# voltage_translation.net
KiCad netlist of a schematic drawn in Altium Designer
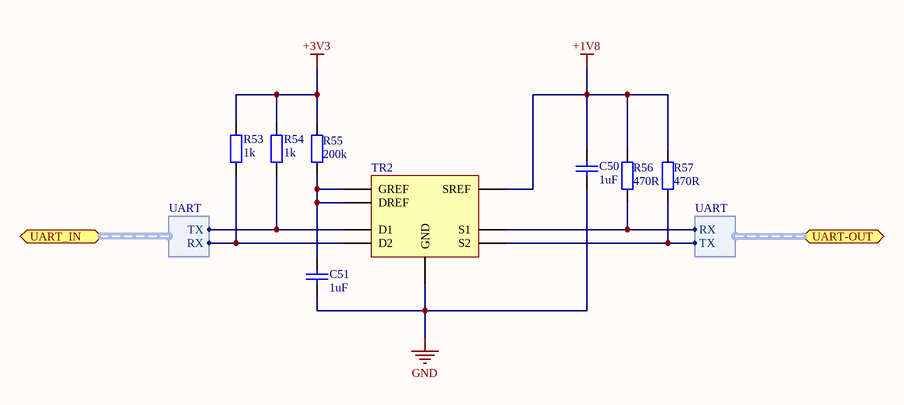
[diagram p0: voltage_translation.SchDoc]

(export (version "E")
  (design (tool "Eeschema 10.0.6"))
  (components
    (comp (ref "C50")
      (value "1uF")
      (footprint "C2012")
      (description "Capacitor")
      (fields
        (field (name "MANUFACTURER") "MULTICOMP")
        (field (name "MANUFACTURER PART NUMBER") "MC0805B105K250CT")
        (field (name "PUBLISHER") "Altium Limited")
      )
      (libsource (lib "Miscellaneous Devices") (part "Cap"))
    )
    (comp (ref "C51")
      (value "1uF")
      (footprint "C2012")
      (description "Capacitor")
      (fields
        (field (name "MANUFACTURER") "MULTICOMP")
        (field (name "MANUFACTURER PART NUMBER") "MC0805B105K250CT")
        (field (name "PUBLISHER") "Altium Limited")
      )
      (libsource (lib "Miscellaneous Devices") (part "Cap"))
    )
    (comp (ref "R53")
      (value "1k")
      (footprint "R2012")
      (description "Resistor")
      (fields
        (field (name "MANUFACTURER") "MULTICOMP")
        (field (name "MANUFACTURER PART NUMBER") "MC01W0805110K")
        (field (name "PUBLISHER") "Altium Limited")
      )
      (libsource (lib "") (part "Res2_1"))
    )
    (comp (ref "R54")
      (value "1k")
      (footprint "R2012")
      (description "Resistor")
      (fields
        (field (name "MANUFACTURER") "MULTICOMP")
        (field (name "MANUFACTURER PART NUMBER") "MC01W0805110K")
        (field (name "PUBLISHER") "Altium Limited")
      )
      (libsource (lib "") (part "Res2_1"))
    )
    (comp (ref "R55")
      (value "200k")
      (footprint "R2012")
      (description "Resistor")
      (fields
        (field (name "MANUFACTURER") "MULTICOMP")
        (field (name "MANUFACTURER PART NUMBER") "MCSR08X2003FTL")
        (field (name "PUBLISHER") "Altium Limited")
      )
      (libsource (lib "Miscellaneous Devices") (part "Res2"))
    )
    (comp (ref "R56")
      (value "470R")
      (footprint "R2012")
      (description "Resistor")
      (fields
        (field (name "MANUFACTURER") "MULTICOMP")
        (field (name "MANUFACTURER PART NUMBER") "MCSR08X4700FTL")
        (field (name "PUBLISHER") "Altium Limited")
      )
      (libsource (lib "Miscellaneous Devices") (part "Res2"))
    )
    (comp (ref "R57")
      (value "470R")
      (footprint "R2012")
      (description "Resistor")
      (fields
        (field (name "MANUFACTURER") "MULTICOMP")
        (field (name "MANUFACTURER PART NUMBER") "MCSR08X4700FTL")
        (field (name "PUBLISHER") "Altium Limited")
      )
      (libsource (lib "Miscellaneous Devices") (part "Res2"))
    )
    (comp (ref "TR2")
      (value "GTL2002")
      (footprint "SOIC8")
      (description "2-bit bidirectional lo  w voltage translator")
      (libsource (lib "bitbots") (part "GTL2002"))
    )
  )
  (nets
    (net (code "2") (name "+1V8") (class "Default")
      (node (ref "C50") (pin "1") (pinfunction "1_1") (pintype "passive"))
      (node (ref "R56") (pin "2") (pinfunction "2_2") (pintype "passive"))
      (node (ref "R57") (pin "2") (pinfunction "2_2") (pintype "passive"))
      (node (ref "TR2") (pin "2") (pinfunction "SREF_2") (pintype "passive"))
    )
    (net (code "3") (name "+3V3") (class "Default")
      (node (ref "R53") (pin "1") (pinfunction "1_1") (pintype "passive"))
      (node (ref "R54") (pin "1") (pinfunction "1_1") (pintype "passive"))
      (node (ref "R55") (pin "2") (pinfunction "2_2") (pintype "passive"))
    )
    (net (code "5") (name "GND") (class "Default")
      (node (ref "C50") (pin "2") (pinfunction "2_2") (pintype "passive"))
      (node (ref "C51") (pin "2") (pinfunction "2_2") (pintype "passive"))
      (node (ref "TR2") (pin "1") (pinfunction "GND_1") (pintype "passive"))
    )
    (net (code "6") (name "Net-(TR2-D1)") (class "Default")
      (node (ref "R54") (pin "2") (pinfunction "2_2") (pintype "passive"))
      (node (ref "TR2") (pin "6") (pinfunction "D1_6") (pintype "passive"))
    )
    (net (code "7") (name "Net-(TR2-D2)") (class "Default")
      (node (ref "R53") (pin "2") (pinfunction "2_2") (pintype "passive"))
      (node (ref "TR2") (pin "5") (pinfunction "D2_5") (pintype "passive"))
    )
    (net (code "8") (name "Net-(TR2-DREF)") (class "Default")
      (node (ref "C51") (pin "1") (pinfunction "1_1") (pintype "passive"))
      (node (ref "R55") (pin "1") (pinfunction "1_1") (pintype "passive"))
      (node (ref "TR2") (pin "7") (pinfunction "DREF_7") (pintype "passive"))
      (node (ref "TR2") (pin "8") (pinfunction "GREF_8") (pintype "passive"))
    )
    (net (code "9") (name "Net-(TR2-S1)") (class "Default")
      (node (ref "R56") (pin "1") (pinfunction "1_1") (pintype "passive"))
      (node (ref "TR2") (pin "3") (pinfunction "S1_3") (pintype "passive"))
    )
    (net (code "10") (name "Net-(TR2-S2)") (class "Default")
      (node (ref "R57") (pin "1") (pinfunction "1_1") (pintype "passive"))
      (node (ref "TR2") (pin "4") (pinfunction "S2_4") (pintype "passive"))
    )
  )
)
